# DO.net
KiCad netlist of a schematic drawn in Altium Designer
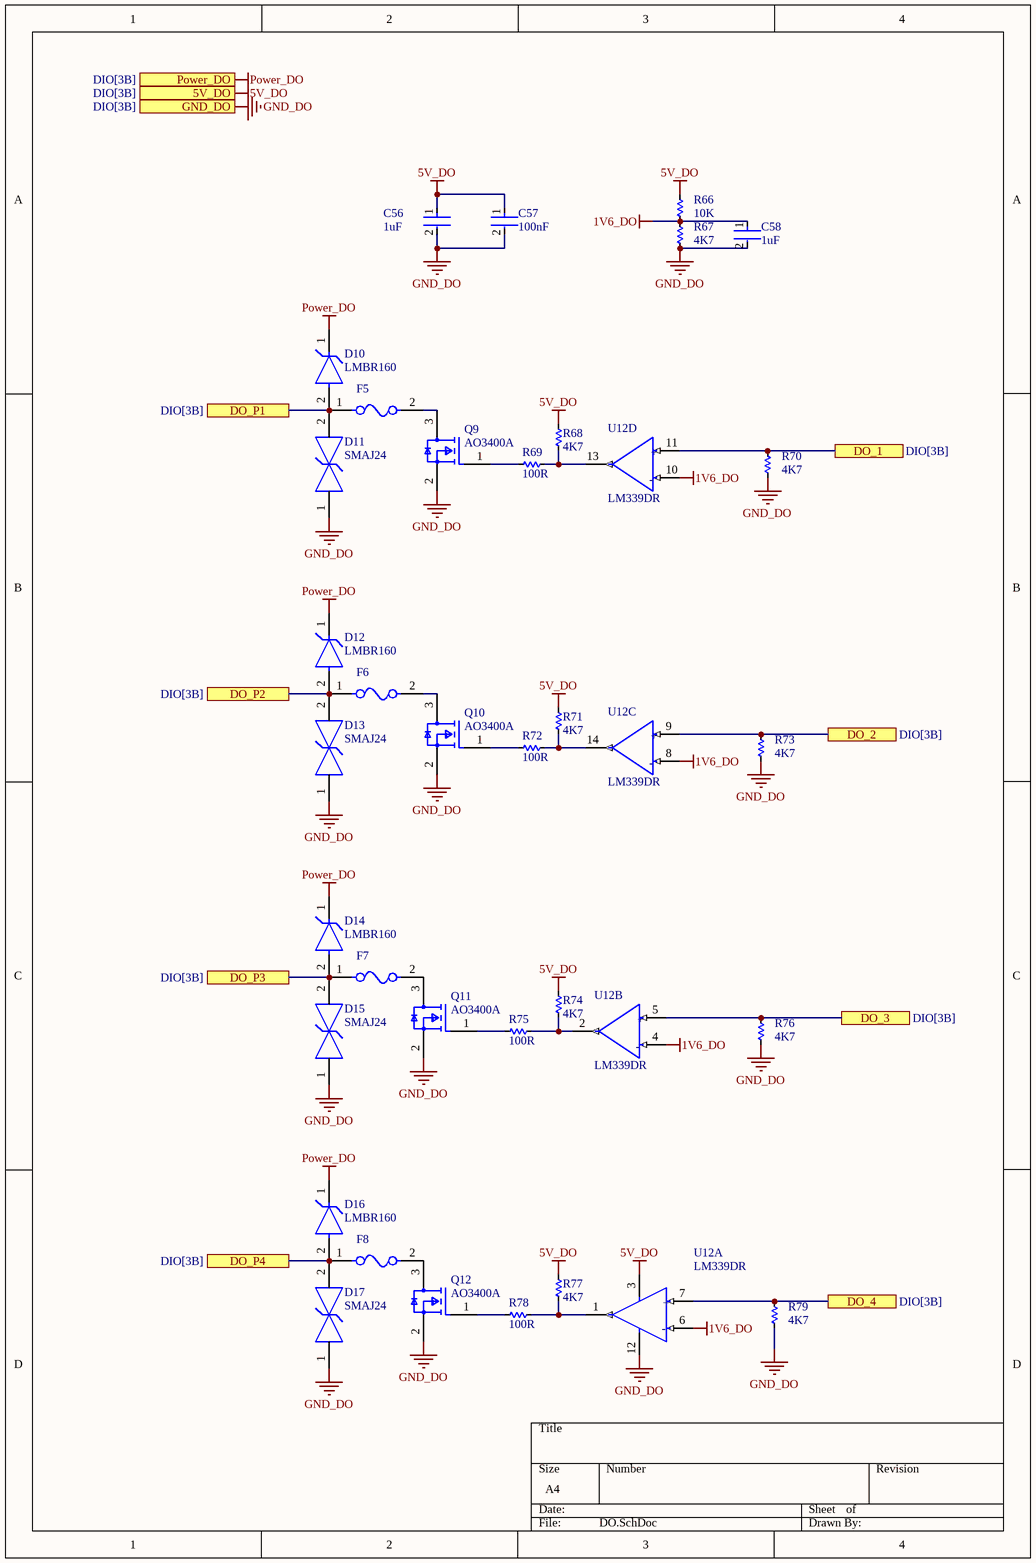
[diagram p0: DO.SchDoc]

(export (version "E")
  (design (tool "Eeschema 10.0.6"))
  (components
    (comp (ref "C56")
      (value "1uF")
      (footprint "FP-GRM18-0_15-MFG")
      (description "CAP CER 1UF 10V X5R 0603")
      (fields
        (field (name "OCTOPART") "https://octopart.com/grm188r61a106ke69d-murata-22851381")
        (field (name "MANUFACTURER PART NUMBER") "GRM188R61A106KE69D")
      )
      (libsource (lib "Altium Content Vault") (part "11868f565c42a9108669ba33697ecf6"))
    )
    (comp (ref "C57")
      (value "100nF")
      (footprint "FP-GRM18-0_15-MFG")
      (description "CAP CER 100nF 10V X5R 0603")
      (fields
        (field (name "OCTOPART") "https://octopart.com/grm188r61a106ke69d-murata-22851381")
        (field (name "MANUFACTURER PART NUMBER") "GRM188R61A106KE69D")
      )
      (libsource (lib "Altium Content Vault") (part "11868f565c42a9108669ba33697ecf6"))
    )
    (comp (ref "C58")
      (value "1uF")
      (footprint "FP-GRM18-0_15-MFG")
      (description "CAP CER 1uF 10V X5R 0603")
      (fields
        (field (name "OCTOPART") "https://octopart.com/grm188r61a106ke69d-murata-22851381")
        (field (name "MANUFACTURER PART NUMBER") "GRM188R61A106KE69D")
      )
      (libsource (lib "Altium Content Vault") (part "11868f565c42a9108669ba33697ecf6"))
    )
    (comp (ref "D10")
      (value "LMBR160")
      (footprint "FP-SOD123-MFG")
      (description "LMBR160 SOD123 Diode Schottky 1A 60V")
      (fields (field (name "TOLERANCE") "6%"))
      (libsource (lib "Altium Content Vault") (part "f813f71cba58e380607f5dd3caf9714"))
    )
    (comp (ref "D11")
      (value "SMAJ24")
      (footprint "FP-SMAJ-MFG")
      (description "Tvs Diode 24V 38.9V SMA")
      (fields
        (field (name "OCTOPART") "https://octopart.com/smaj58ca-littelfuse-350202")
        (field (name "MANUFACTURER") "Littelfuse Inc")
      )
      (libsource (lib "Altium Content Vault") (part "89c663e49c8877d2c9d183c2997548d"))
    )
    (comp (ref "D12")
      (value "LMBR160")
      (footprint "FP-SOD123-MFG")
      (description "LMBR160 SOD123 Diode Schottky 1A 60V")
      (fields (field (name "TOLERANCE") "6%"))
      (libsource (lib "Altium Content Vault") (part "f813f71cba58e380607f5dd3caf9714"))
    )
    (comp (ref "D13")
      (value "SMAJ24")
      (footprint "FP-SMAJ-MFG")
      (description "Tvs Diode 24V 38.9V SMA")
      (fields
        (field (name "OCTOPART") "https://octopart.com/smaj58ca-littelfuse-350202")
        (field (name "MANUFACTURER") "Littelfuse Inc")
      )
      (libsource (lib "Altium Content Vault") (part "89c663e49c8877d2c9d183c2997548d"))
    )
    (comp (ref "D14")
      (value "LMBR160")
      (footprint "FP-SOD123-MFG")
      (description "LMBR160 SOD123 Diode Schottky 1A 60V")
      (fields (field (name "TOLERANCE") "6%"))
      (libsource (lib "Altium Content Vault") (part "f813f71cba58e380607f5dd3caf9714"))
    )
    (comp (ref "D15")
      (value "SMAJ24")
      (footprint "FP-SMAJ-MFG")
      (description "Tvs Diode 24V 38.9V SMA")
      (fields
        (field (name "OCTOPART") "https://octopart.com/smaj58ca-littelfuse-350202")
        (field (name "MANUFACTURER") "Littelfuse Inc")
      )
      (libsource (lib "Altium Content Vault") (part "89c663e49c8877d2c9d183c2997548d"))
    )
    (comp (ref "D16")
      (value "LMBR160")
      (footprint "FP-SOD123-MFG")
      (description "LMBR160 SOD123 Diode Schottky 1A 60V")
      (fields (field (name "TOLERANCE") "6%"))
      (libsource (lib "Altium Content Vault") (part "f813f71cba58e380607f5dd3caf9714"))
    )
    (comp (ref "D17")
      (value "SMAJ24")
      (footprint "FP-SMAJ-MFG")
      (description "Tvs Diode 24V 38.9V SMA")
      (fields
        (field (name "OCTOPART") "https://octopart.com/smaj58ca-littelfuse-350202")
        (field (name "MANUFACTURER") "Littelfuse Inc")
      )
      (libsource (lib "Altium Content Vault") (part "89c663e49c8877d2c9d183c2997548d"))
    )
    (comp (ref "F5")
      (value "2A 30V")
      (footprint "FP-0468-MFG")
      (description "SMD1206P200TF/30 Cầu chì tự phục hồi PPTC 2A 30V SMD1206")
      (fields
        (field (name "MANUFACTURER PART NUMBER") "0468.500NR")
        (field (name "OCTOPART") "https://octopart.com/0468.500nr-littelfuse-672821")
      )
      (libsource (lib "Altium Content Vault") (part "5bcf9b9f640e542cf0359d10258e979"))
    )
    (comp (ref "F6")
      (value "2A 30V")
      (footprint "FP-0468-MFG")
      (description "SMD1206P200TF/30 Cầu chì tự phục hồi PPTC 2A 30V SMD1206")
      (fields
        (field (name "MANUFACTURER PART NUMBER") "0468.500NR")
        (field (name "OCTOPART") "https://octopart.com/0468.500nr-littelfuse-672821")
      )
      (libsource (lib "Altium Content Vault") (part "5bcf9b9f640e542cf0359d10258e979"))
    )
    (comp (ref "F7")
      (value "2A 30V")
      (footprint "FP-0468-MFG")
      (description "SMD1206P200TF/30 Cầu chì tự phục hồi PPTC 2A 30V SMD1206")
      (fields
        (field (name "MANUFACTURER PART NUMBER") "0468.500NR")
        (field (name "OCTOPART") "https://octopart.com/0468.500nr-littelfuse-672821")
      )
      (libsource (lib "Altium Content Vault") (part "5bcf9b9f640e542cf0359d10258e979"))
    )
    (comp (ref "F8")
      (value "2A 30V")
      (footprint "FP-0468-MFG")
      (description "SMD1206P200TF/30 Cầu chì tự phục hồi PPTC 2A 30V SMD1206")
      (fields
        (field (name "MANUFACTURER PART NUMBER") "0468.500NR")
        (field (name "OCTOPART") "https://octopart.com/0468.500nr-littelfuse-672821")
      )
      (libsource (lib "Altium Content Vault") (part "5bcf9b9f640e542cf0359d10258e979"))
    )
    (comp (ref "Q9")
      (value "AO3400A")
      (footprint "FP-SOT23-MFG")
      (description "AO3400 SOT23-3 MOSFET N-1CH 5A 30V (A09T)")
      (libsource (lib "Altium Content Vault") (part "0a9ea7c96deaaede766a5b531c28de0"))
    )
    (comp (ref "Q10")
      (value "AO3400A")
      (footprint "FP-SOT23-MFG")
      (description "AO3400 SOT23-3 MOSFET N-1CH 5A 30V (A09T)")
      (libsource (lib "Altium Content Vault") (part "0a9ea7c96deaaede766a5b531c28de0"))
    )
    (comp (ref "Q11")
      (value "AO3400A")
      (footprint "FP-SOT23-MFG")
      (description "AO3400 SOT23-3 MOSFET N-1CH 5A 30V (A09T)")
      (libsource (lib "Altium Content Vault") (part "0a9ea7c96deaaede766a5b531c28de0"))
    )
    (comp (ref "Q12")
      (value "AO3400A")
      (footprint "FP-SOT23-MFG")
      (description "AO3400 SOT23-3 MOSFET N-1CH 5A 30V (A09T)")
      (libsource (lib "Altium Content Vault") (part "0a9ea7c96deaaede766a5b531c28de0"))
    )
    (comp (ref "R66")
      (value "10K")
      (footprint "RES-SMD-0603")
      (description "Res 0603 5%")
      (fields
        (field (name "MANUFACTURER") "Generic Components")
        (field (name "PUBLISHER") "Altium Hobart Technology Centre")
      )
      (libsource (lib "TechMT.VN_Lib_Project v2") (part "Res-SMD"))
    )
    (comp (ref "R67")
      (value "4K7")
      (footprint "RES-SMD-0603")
      (description "Res 0603 5%")
      (fields
        (field (name "MANUFACTURER") "Generic Components")
        (field (name "PUBLISHER") "Altium Hobart Technology Centre")
      )
      (libsource (lib "TechMT.VN_Lib_Project v2") (part "Res-SMD"))
    )
    (comp (ref "R68")
      (value "4K7")
      (footprint "RES-SMD-0603")
      (description "Res 0603 5%")
      (fields
        (field (name "MANUFACTURER") "Generic Components")
        (field (name "PUBLISHER") "Altium Hobart Technology Centre")
      )
      (libsource (lib "TechMT.VN_Lib_Project v2") (part "Res-SMD"))
    )
    (comp (ref "R69")
      (value "100R")
      (footprint "RES-SMD-0603")
      (description "Res 0603 5%")
      (fields
        (field (name "MANUFACTURER") "Generic Components")
        (field (name "PUBLISHER") "Altium Hobart Technology Centre")
      )
      (libsource (lib "TechMT.VN_Lib_Project v2") (part "Res-SMD"))
    )
    (comp (ref "R70")
      (value "4K7")
      (footprint "RES-SMD-0603")
      (description "Res 0603 5%")
      (fields
        (field (name "MANUFACTURER") "Generic Components")
        (field (name "PUBLISHER") "Altium Hobart Technology Centre")
      )
      (libsource (lib "TechMT.VN_Lib_Project v2") (part "Res-SMD"))
    )
    (comp (ref "R71")
      (value "4K7")
      (footprint "RES-SMD-0603")
      (description "Res 0603 5%")
      (fields
        (field (name "MANUFACTURER") "Generic Components")
        (field (name "PUBLISHER") "Altium Hobart Technology Centre")
      )
      (libsource (lib "TechMT.VN_Lib_Project v2") (part "Res-SMD"))
    )
    (comp (ref "R72")
      (value "100R")
      (footprint "RES-SMD-0603")
      (description "Res 0603 5%")
      (fields
        (field (name "MANUFACTURER") "Generic Components")
        (field (name "PUBLISHER") "Altium Hobart Technology Centre")
      )
      (libsource (lib "TechMT.VN_Lib_Project v2") (part "Res-SMD"))
    )
    (comp (ref "R73")
      (value "4K7")
      (footprint "RES-SMD-0603")
      (description "Res 0603 5%")
      (fields
        (field (name "MANUFACTURER") "Generic Components")
        (field (name "PUBLISHER") "Altium Hobart Technology Centre")
      )
      (libsource (lib "TechMT.VN_Lib_Project v2") (part "Res-SMD"))
    )
    (comp (ref "R74")
      (value "4K7")
      (footprint "RES-SMD-0603")
      (description "Res 0603 5%")
      (fields
        (field (name "MANUFACTURER") "Generic Components")
        (field (name "PUBLISHER") "Altium Hobart Technology Centre")
      )
      (libsource (lib "TechMT.VN_Lib_Project v2") (part "Res-SMD"))
    )
    (comp (ref "R75")
      (value "100R")
      (footprint "RES-SMD-0603")
      (description "Res 0603 5%")
      (fields
        (field (name "MANUFACTURER") "Generic Components")
        (field (name "PUBLISHER") "Altium Hobart Technology Centre")
      )
      (libsource (lib "TechMT.VN_Lib_Project v2") (part "Res-SMD"))
    )
    (comp (ref "R76")
      (value "4K7")
      (footprint "RES-SMD-0603")
      (description "Res 0603 5%")
      (fields
        (field (name "MANUFACTURER") "Generic Components")
        (field (name "PUBLISHER") "Altium Hobart Technology Centre")
      )
      (libsource (lib "TechMT.VN_Lib_Project v2") (part "Res-SMD"))
    )
    (comp (ref "R77")
      (value "4K7")
      (footprint "RES-SMD-0603")
      (description "Res 0603 5%")
      (fields
        (field (name "MANUFACTURER") "Generic Components")
        (field (name "PUBLISHER") "Altium Hobart Technology Centre")
      )
      (libsource (lib "TechMT.VN_Lib_Project v2") (part "Res-SMD"))
    )
    (comp (ref "R78")
      (value "100R")
      (footprint "RES-SMD-0603")
      (description "Res 0603 5%")
      (fields
        (field (name "MANUFACTURER") "Generic Components")
        (field (name "PUBLISHER") "Altium Hobart Technology Centre")
      )
      (libsource (lib "TechMT.VN_Lib_Project v2") (part "Res-SMD"))
    )
    (comp (ref "R79")
      (value "4K7")
      (footprint "RES-SMD-0603")
      (description "Res 0603 5%")
      (fields
        (field (name "MANUFACTURER") "Generic Components")
        (field (name "PUBLISHER") "Altium Hobart Technology Centre")
      )
      (libsource (lib "TechMT.VN_Lib_Project v2") (part "Res-SMD"))
    )
    (comp (ref "U12")
      (value "LM339DR")
      (footprint "FP-D0014A-IPC_A")
      (description "IC QUAD DIFF COMP 14-SOIC")
      (fields
        (field (name "OCTOPART") "https://octopart.com/lm339dr-texas+instruments-45532")
        (field (name "MANUFACTURER") "Texas Instruments")
      )
      (libsource (lib "Altium Content Vault") (part "e40d3f79f05c88e03941af0c3538ad1"))
    )
  )
  (nets
    (net (code "1") (name "/DO_1") (class "Default")
      (node (ref "R70") (pin "1") (pinfunction "1_1") (pintype "passive"))
      (node (ref "U12") (pin "11") (pinfunction "4IN+_11") (pintype "input"))
    )
    (net (code "2") (name "/DO_2") (class "Default")
      (node (ref "R73") (pin "1") (pinfunction "1_1") (pintype "passive"))
      (node (ref "U12") (pin "9") (pinfunction "3IN+_9") (pintype "input"))
    )
    (net (code "3") (name "/DO_3") (class "Default")
      (node (ref "R76") (pin "1") (pinfunction "1_1") (pintype "passive"))
      (node (ref "U12") (pin "5") (pinfunction "2IN+_5") (pintype "input"))
    )
    (net (code "4") (name "/DO_4") (class "Default")
      (node (ref "R79") (pin "1") (pinfunction "1_1") (pintype "passive"))
      (node (ref "U12") (pin "7") (pinfunction "1IN+_7") (pintype "input"))
    )
    (net (code "5") (name "/DO_P1") (class "Default")
      (node (ref "D10") (pin "2") (pinfunction "A_2") (pintype "passive"))
      (node (ref "D11") (pin "2") (pinfunction "2_2") (pintype "passive"))
      (node (ref "F5") (pin "1") (pinfunction "1_1") (pintype "passive"))
    )
    (net (code "6") (name "/DO_P2") (class "Default")
      (node (ref "D12") (pin "2") (pinfunction "A_2") (pintype "passive"))
      (node (ref "D13") (pin "2") (pinfunction "2_2") (pintype "passive"))
      (node (ref "F6") (pin "1") (pinfunction "1_1") (pintype "passive"))
    )
    (net (code "7") (name "/DO_P3") (class "Default")
      (node (ref "D14") (pin "2") (pinfunction "A_2") (pintype "passive"))
      (node (ref "D15") (pin "2") (pinfunction "2_2") (pintype "passive"))
      (node (ref "F7") (pin "1") (pinfunction "1_1") (pintype "passive"))
    )
    (net (code "8") (name "/DO_P4") (class "Default")
      (node (ref "D16") (pin "2") (pinfunction "A_2") (pintype "passive"))
      (node (ref "D17") (pin "2") (pinfunction "2_2") (pintype "passive"))
      (node (ref "F8") (pin "1") (pinfunction "1_1") (pintype "passive"))
    )
    (net (code "9") (name "1V6_DO") (class "Default")
      (node (ref "C58") (pin "1") (pinfunction "1_1") (pintype "passive"))
      (node (ref "R66") (pin "2") (pinfunction "2_2") (pintype "passive"))
      (node (ref "R67") (pin "1") (pinfunction "1_1") (pintype "passive"))
      (node (ref "U12") (pin "10") (pinfunction "4IN-_10") (pintype "input"))
      (node (ref "U12") (pin "4") (pinfunction "2IN-_4") (pintype "input"))
      (node (ref "U12") (pin "6") (pinfunction "1IN-_6") (pintype "input"))
      (node (ref "U12") (pin "8") (pinfunction "3IN-_8") (pintype "input"))
    )
    (net (code "10") (name "5V_DO") (class "Default")
      (node (ref "C56") (pin "1") (pinfunction "1_1") (pintype "passive"))
      (node (ref "C57") (pin "1") (pinfunction "1_1") (pintype "passive"))
      (node (ref "R66") (pin "1") (pinfunction "1_1") (pintype "passive"))
      (node (ref "R68") (pin "2") (pinfunction "2_2") (pintype "passive"))
      (node (ref "R71") (pin "2") (pinfunction "2_2") (pintype "passive"))
      (node (ref "R74") (pin "2") (pinfunction "2_2") (pintype "passive"))
      (node (ref "R77") (pin "2") (pinfunction "2_2") (pintype "passive"))
      (node (ref "U12") (pin "3") (pinfunction "VCC_3") (pintype "power_in"))
    )
    (net (code "11") (name "GND_DO") (class "Default")
      (node (ref "C56") (pin "2") (pinfunction "2_2") (pintype "passive"))
      (node (ref "C57") (pin "2") (pinfunction "2_2") (pintype "passive"))
      (node (ref "C58") (pin "2") (pinfunction "2_2") (pintype "passive"))
      (node (ref "D11") (pin "1") (pinfunction "1_1") (pintype "passive"))
      (node (ref "D13") (pin "1") (pinfunction "1_1") (pintype "passive"))
      (node (ref "D15") (pin "1") (pinfunction "1_1") (pintype "passive"))
      (node (ref "D17") (pin "1") (pinfunction "1_1") (pintype "passive"))
      (node (ref "Q10") (pin "2") (pinfunction "S_2") (pintype "passive"))
      (node (ref "Q11") (pin "2") (pinfunction "S_2") (pintype "passive"))
      (node (ref "Q12") (pin "2") (pinfunction "S_2") (pintype "passive"))
      (node (ref "Q9") (pin "2") (pinfunction "S_2") (pintype "passive"))
      (node (ref "R67") (pin "2") (pinfunction "2_2") (pintype "passive"))
      (node (ref "R70") (pin "2") (pinfunction "2_2") (pintype "passive"))
      (node (ref "R73") (pin "2") (pinfunction "2_2") (pintype "passive"))
      (node (ref "R76") (pin "2") (pinfunction "2_2") (pintype "passive"))
      (node (ref "R79") (pin "2") (pinfunction "2_2") (pintype "passive"))
      (node (ref "U12") (pin "12") (pinfunction "GND_12") (pintype "power_in"))
    )
    (net (code "12") (name "Net-(Q9-D)") (class "Default")
      (node (ref "F5") (pin "2") (pinfunction "2_2") (pintype "passive"))
      (node (ref "Q9") (pin "3") (pinfunction "D_3") (pintype "passive"))
    )
    (net (code "13") (name "Net-(Q9-G)") (class "Default")
      (node (ref "Q9") (pin "1") (pinfunction "G_1") (pintype "passive"))
      (node (ref "R69") (pin "1") (pinfunction "1_1") (pintype "passive"))
    )
    (net (code "14") (name "Net-(Q10-D)") (class "Default")
      (node (ref "F6") (pin "2") (pinfunction "2_2") (pintype "passive"))
      (node (ref "Q10") (pin "3") (pinfunction "D_3") (pintype "passive"))
    )
    (net (code "15") (name "Net-(Q10-G)") (class "Default")
      (node (ref "Q10") (pin "1") (pinfunction "G_1") (pintype "passive"))
      (node (ref "R72") (pin "1") (pinfunction "1_1") (pintype "passive"))
    )
    (net (code "16") (name "Net-(Q11-D)") (class "Default")
      (node (ref "F7") (pin "2") (pinfunction "2_2") (pintype "passive"))
      (node (ref "Q11") (pin "3") (pinfunction "D_3") (pintype "passive"))
    )
    (net (code "17") (name "Net-(Q11-G)") (class "Default")
      (node (ref "Q11") (pin "1") (pinfunction "G_1") (pintype "passive"))
      (node (ref "R75") (pin "1") (pinfunction "1_1") (pintype "passive"))
    )
    (net (code "18") (name "Net-(Q12-D)") (class "Default")
      (node (ref "F8") (pin "2") (pinfunction "2_2") (pintype "passive"))
      (node (ref "Q12") (pin "3") (pinfunction "D_3") (pintype "passive"))
    )
    (net (code "19") (name "Net-(Q12-G)") (class "Default")
      (node (ref "Q12") (pin "1") (pinfunction "G_1") (pintype "passive"))
      (node (ref "R78") (pin "1") (pinfunction "1_1") (pintype "passive"))
    )
    (net (code "20") (name "Net-(U12A-1OUT)") (class "Default")
      (node (ref "R77") (pin "1") (pinfunction "1_1") (pintype "passive"))
      (node (ref "R78") (pin "2") (pinfunction "2_2") (pintype "passive"))
      (node (ref "U12") (pin "1") (pinfunction "1OUT_1") (pintype "output"))
    )
    (net (code "21") (name "Net-(U12B-2OUT)") (class "Default")
      (node (ref "R74") (pin "1") (pinfunction "1_1") (pintype "passive"))
      (node (ref "R75") (pin "2") (pinfunction "2_2") (pintype "passive"))
      (node (ref "U12") (pin "2") (pinfunction "2OUT_2") (pintype "output"))
    )
    (net (code "22") (name "Net-(U12C-OUT3)") (class "Default")
      (node (ref "R71") (pin "1") (pinfunction "1_1") (pintype "passive"))
      (node (ref "R72") (pin "2") (pinfunction "2_2") (pintype "passive"))
      (node (ref "U12") (pin "14") (pinfunction "OUT3_14") (pintype "output"))
    )
    (net (code "23") (name "Net-(U12D-OUT4)") (class "Default")
      (node (ref "R68") (pin "1") (pinfunction "1_1") (pintype "passive"))
      (node (ref "R69") (pin "2") (pinfunction "2_2") (pintype "passive"))
      (node (ref "U12") (pin "13") (pinfunction "OUT4_13") (pintype "output"))
    )
    (net (code "24") (name "Power_DO") (class "Default")
      (node (ref "D10") (pin "1") (pinfunction "C_1") (pintype "passive"))
      (node (ref "D12") (pin "1") (pinfunction "C_1") (pintype "passive"))
      (node (ref "D14") (pin "1") (pinfunction "C_1") (pintype "passive"))
      (node (ref "D16") (pin "1") (pinfunction "C_1") (pintype "passive"))
    )
  )
)
